# PT4115_circiut_design.net
KiCad netlist of a schematic drawn in EAGLE
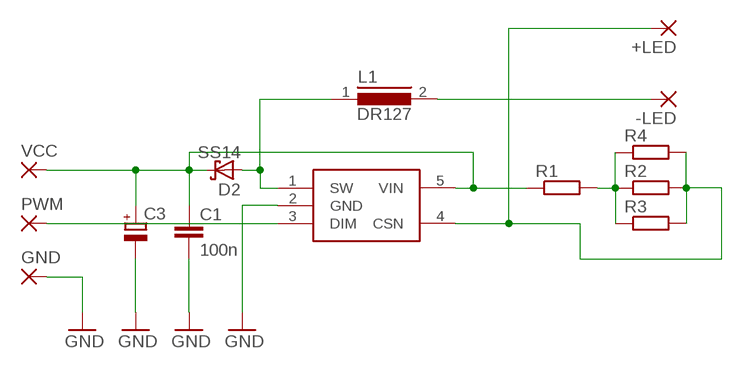
[diagram p0: schematic, sheet 1]

(export (version "E")
  (design (tool "Eeschema 10.0.6"))
  (components
    (comp (ref "+LED")
      (value "SMD5")
      (footprint "eagle-import:SMD2,54-5,08")
      (libsource (lib "eagle-import") (part "SMD5"))
    )
    (comp (ref "-LED")
      (value "SMD5")
      (footprint "eagle-import:SMD2,54-5,08")
      (libsource (lib "eagle-import") (part "SMD5"))
    )
    (comp (ref "C1")
      (value "100n")
      (footprint "eagle-import:C0805")
      (libsource (lib "eagle-import") (part "C-EUC0805"))
    )
    (comp (ref "C3")
      (value "CPOL-EUSMCD")
      (footprint "eagle-import:SMC_D")
      (libsource (lib "eagle-import") (part "CPOL-EUSMCD"))
    )
    (comp (ref "D2")
      (value "SS14")
      (footprint "eagle-import:DO-214AC")
      (fields (field (name "MF") "ON Semiconductor"))
      (libsource (lib "eagle-import") (part "SS14"))
    )
    (comp (ref "GND")
      (value "SMD5")
      (footprint "eagle-import:SMD2,54-5,08")
      (libsource (lib "eagle-import") (part "SMD5"))
    )
    (comp (ref "L1")
      (value "DR127")
      (footprint "eagle-import:DR127")
      (libsource (lib "eagle-import") (part "DR127"))
    )
    (comp (ref "PWM")
      (value "SMD5")
      (footprint "eagle-import:SMD2,54-5,08")
      (libsource (lib "eagle-import") (part "SMD5"))
    )
    (comp (ref "R1")
      (value "R-EU_M0805")
      (footprint "eagle-import:M0805")
      (libsource (lib "eagle-import") (part "R-EU_M0805"))
    )
    (comp (ref "R2")
      (value "R-EU_M0805")
      (footprint "eagle-import:M0805")
      (libsource (lib "eagle-import") (part "R-EU_M0805"))
    )
    (comp (ref "R3")
      (value "R-EU_M0805")
      (footprint "eagle-import:M0805")
      (libsource (lib "eagle-import") (part "R-EU_M0805"))
    )
    (comp (ref "R4")
      (value "R-EU_M0805")
      (footprint "eagle-import:M0805")
      (libsource (lib "eagle-import") (part "R-EU_M0805"))
    )
    (comp (ref "U$1")
      (value "PT4115")
      (footprint "eagle-import:SOT-89-5")
      (fields (field (name "MF") "Pulse"))
      (libsource (lib "eagle-import") (part "PT4115"))
    )
    (comp (ref "VCC")
      (value "SMD5")
      (footprint "eagle-import:SMD2,54-5,08")
      (libsource (lib "eagle-import") (part "SMD5"))
    )
  )
  (nets
    (net (code "1") (name "GND") (class "Default")
      (node (ref "C1") (pin "2") (pinfunction "2_2") (pintype "passive"))
      (node (ref "C3") (pin "-") (pinfunction "-_-") (pintype "passive"))
      (node (ref "GND") (pin "1") (pinfunction "P_1") (pintype "passive"))
      (node (ref "U$1") (pin "2") (pinfunction "GND_2") (pintype "bidirectional"))
    )
    (net (code "2") (name "Net-(+LED-P)") (class "Default")
      (node (ref "+LED") (pin "1") (pinfunction "P_1") (pintype "passive"))
      (node (ref "R2") (pin "2") (pinfunction "2_2") (pintype "passive"))
      (node (ref "R3") (pin "2") (pinfunction "2_2") (pintype "passive"))
      (node (ref "R4") (pin "2") (pinfunction "2_2") (pintype "passive"))
      (node (ref "U$1") (pin "4") (pinfunction "CSN_4") (pintype "bidirectional"))
    )
    (net (code "3") (name "Net-(-LED-P)") (class "Default")
      (node (ref "-LED") (pin "1") (pinfunction "P_1") (pintype "passive"))
      (node (ref "L1") (pin "2") (pinfunction "2_2") (pintype "passive"))
    )
    (net (code "4") (name "Net-(PWM-P)") (class "Default")
      (node (ref "PWM") (pin "1") (pinfunction "P_1") (pintype "passive"))
      (node (ref "U$1") (pin "3") (pinfunction "DIM_3") (pintype "bidirectional"))
    )
    (net (code "5") (name "Net-(R1-Pad2)") (class "Default")
      (node (ref "R1") (pin "2") (pinfunction "2_2") (pintype "passive"))
      (node (ref "R2") (pin "1") (pinfunction "1_1") (pintype "passive"))
      (node (ref "R3") (pin "1") (pinfunction "1_1") (pintype "passive"))
      (node (ref "R4") (pin "1") (pinfunction "1_1") (pintype "passive"))
    )
    (net (code "6") (name "Net-(U$1-SW)") (class "Default")
      (node (ref "D2") (pin "A") (pinfunction "A_A") (pintype "passive"))
      (node (ref "L1") (pin "1") (pinfunction "1_1") (pintype "passive"))
      (node (ref "U$1") (pin "1") (pinfunction "SW_1") (pintype "bidirectional"))
    )
    (net (code "7") (name "Net-(U$1-VIN)") (class "Default")
      (node (ref "C1") (pin "1") (pinfunction "1_1") (pintype "passive"))
      (node (ref "C3") (pin "+") (pinfunction "+_+") (pintype "passive"))
      (node (ref "D2") (pin "K") (pinfunction "K_K") (pintype "passive"))
      (node (ref "R1") (pin "1") (pinfunction "1_1") (pintype "passive"))
      (node (ref "U$1") (pin "5") (pinfunction "VIN_5") (pintype "bidirectional"))
      (node (ref "VCC") (pin "1") (pinfunction "P_1") (pintype "passive"))
    )
  )
)
